# Stabilizer_Piezo_Driver.net
KiCad netlist of a schematic drawn in Altium Designer
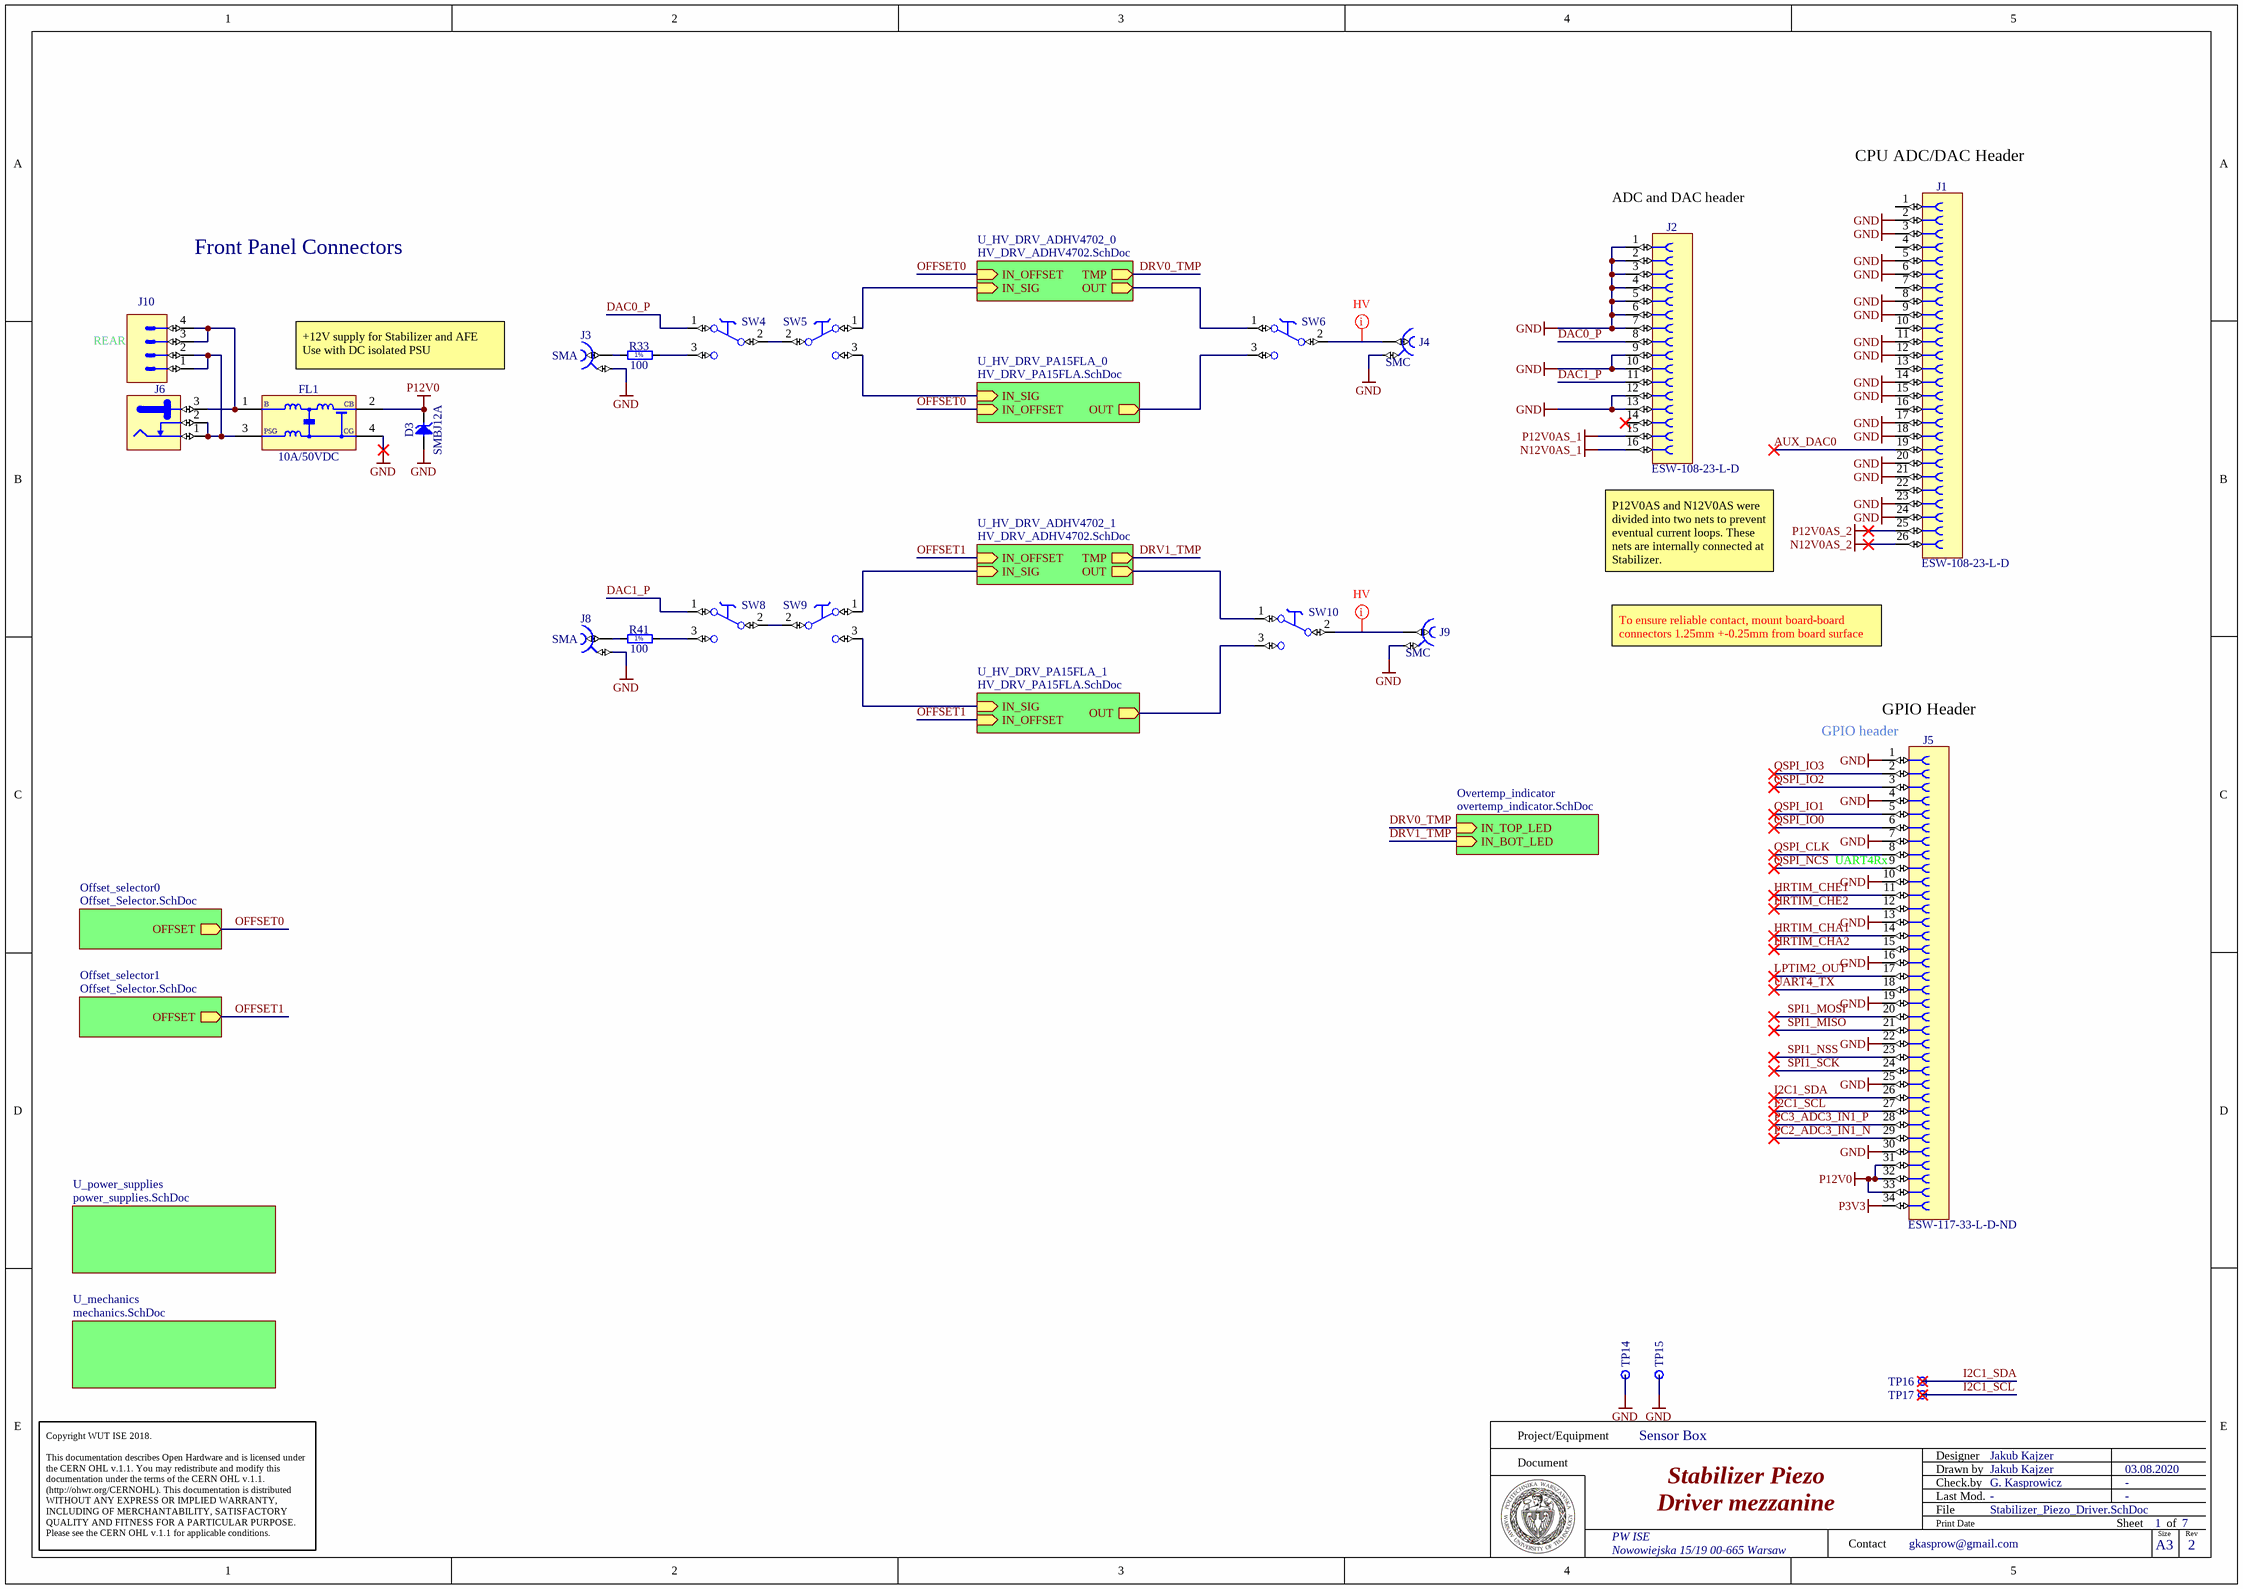
[diagram p0: Stabilizer_Piezo_Driver.SchDoc]

(export (version "E")
  (design (tool "Eeschema 10.0.6"))
  (components
    (comp (ref "D3")
      (value "SMBJ12A")
      (footprint "DIOM5336X265N")
      (description "Zener Diode")
      (fields
        (field (name "VOLTAGE") "12V")
        (field (name "POWER") "600W")
        (field (name "AUTHOR") "CERN DEM JLC")
      )
      (libsource (lib "ICs And Semiconductors") (part "Diode Zener"))
    )
    (comp (ref "FL1")
      (value "10A/50VDC")
      (footprint "FIL_MURATA_BNX02")
      (description "Block Type EMIFIL (LC Combined)")
      (fields
        (field (name "PART NUMBER") "FIL_MURATA_BNX022-01L")
        (field (name "MANUFACTURER") "MURATA")
        (field (name "AUTHOR") "CERN DEM JLC")
      )
      (libsource (lib "Inductors & Transformers") (part "FIL_MURATA_BNX02"))
    )
    (comp (ref "J1")
      (value "ESW-108-23-L-D")
      (footprint "connectors:ESW-113-23-L-D")
      (description "Connector Elevated Socket 26 POS 2.54mm, 13.59mm height")
      (fields
        (field (name "MANUFACTURER") "Samtec")
        (field (name "MANUFACTURER PART NUMBER") "ESW-108-23-L-D")
      )
      (libsource (lib "connectors") (part "ESW-113-23-L-D"))
    )
    (comp (ref "J2")
      (value "ESW-108-23-L-D")
      (footprint "connectors:ESW-108-23-L-D")
      (description "Connector Elevated Socket 16 POS 2.54mm, 13.59mm height")
      (fields
        (field (name "MANUFACTURER") "Samtec")
        (field (name "MANUFACTURER PART NUMBER") "ESW-108-23-L-D")
      )
      (libsource (lib "connectors") (part "ESW-108-23-L-D"))
    )
    (comp (ref "J3")
      (value "SMA")
      (footprint "RF249BT0050GHDW")
      (description "50 Ohm Through Hole SMA Right Angle PCB Jack")
      (fields
        (field (name "PART NUMBER") "AdamTech_RF249BT0050GHDW")
        (field (name "MANUFACTURER") "AdamTech")
        (field (name "AUTHOR") "GK")
      )
      (libsource (lib "LIBRARY_SCH") (part "CON_SMA_RF249BT0050GHDW"))
    )
    (comp (ref "J4")
      (value "SMC")
      (footprint "JOHNSON_131-6701-341")
      (fields
        (field (name "PART NUMBER") "JOHNSON_131-6701-341")
        (field (name "MANUFACTURER") "JOHNSON")
        (field (name "MANUFACTURER PART NUMBER") "131-6701-341")
        (field (name "AUTHOR") "CERN DEM JLC")
      )
      (libsource (lib "Connectors") (part "Coax_1Female_1Shield"))
    )
    (comp (ref "J5")
      (value "ESW-108-23-L-D")
      (footprint "connectors:ESW-117-23-L-D")
      (description "Connector Elevated Socket 34 POS 2.54mm, 13.59mm height")
      (fields
        (field (name "MANUFACTURER") "Samtec")
        (field (name "MANUFACTURER PART NUMBER") "ESW-117-33-L-D-ND")
      )
      (libsource (lib "connectors") (part "ESW-117-23-L-D"))
    )
    (comp (ref "J6")
      (value "Jack")
      (footprint "Library-connectors:SWITCHCRAFT_L712RA")
      (description "24V /3. 5A, 2.1mm Diameter Pin, SMD DC Power Supply Connector With  Break Contact")
      (fields
        (field (name "PART NUMBER") "SWITCHCRAFT_L712RA")
        (field (name "MANUFACTURER") "SWITCHCRAFT")
        (field (name "AUTHOR") "GK")
      )
      (libsource (lib "LIBRARY_SCH") (part "CON_DC_5A_THT_RA"))
    )
    (comp (ref "J8")
      (value "SMA")
      (footprint "RF249BT0050GHDW")
      (description "50 Ohm Through Hole SMA Right Angle PCB Jack")
      (fields
        (field (name "PART NUMBER") "AdamTech_RF249BT0050GHDW")
        (field (name "MANUFACTURER") "AdamTech")
        (field (name "AUTHOR") "GK")
      )
      (libsource (lib "LIBRARY_SCH") (part "CON_SMA_RF249BT0050GHDW"))
    )
    (comp (ref "J9")
      (value "SMC")
      (footprint "JOHNSON_131-6701-341")
      (fields
        (field (name "PART NUMBER") "JOHNSON_131-6701-341")
        (field (name "MANUFACTURER") "JOHNSON")
        (field (name "MANUFACTURER PART NUMBER") "131-6701-341")
        (field (name "AUTHOR") "CERN DEM JLC")
      )
      (libsource (lib "Connectors") (part "Coax_1Female_1Shield"))
    )
    (comp (ref "J10")
      (value "Mini-Fit Jr.™")
      (footprint "MOLEX_39-30-0040")
      (description "Connector 4 Male")
      (fields
        (field (name "PART NUMBER") "MOLEX_39-30-0040")
        (field (name "MANUFACTURER") "MOLEX")
        (field (name "AUTHOR") "CERN DEM JLC")
      )
      (libsource (lib "Connectors") (part "Connector 4 Male"))
    )
    (comp (ref "R33")
      (value "100")
      (footprint "RESC1005X40N")
      (description "Resistor - 1%")
      (fields
        (field (name "PART NUMBER") "R0402_100R_1%_0.0625W_100PPM")
        (field (name "POWER") "0.0625W")
        (field (name "AUTHOR") "CERN DEM JLC")
      )
      (libsource (lib "Resistors") (part "Resistor - 1%"))
    )
    (comp (ref "R41")
      (value "100")
      (footprint "RESC1005X40N")
      (description "Resistor - 1%")
      (fields
        (field (name "PART NUMBER") "R0402_100R_1%_0.0625W_100PPM")
        (field (name "POWER") "0.0625W")
        (field (name "AUTHOR") "CERN DEM JLC")
      )
      (libsource (lib "Resistors") (part "Resistor - 1%"))
    )
    (comp (ref "SW4")
      (value "Switch")
      (footprint "SW_C&K_1101M2S3CQE2")
      (description "SPDT Switch")
      (fields
        (field (name "PART NUMBER") "SW_C&K_1101M2S3CQE2")
        (field (name "MANUFACTURER") "C&K")
        (field (name "AUTHOR") "CERN DEM BC")
      )
      (libsource (lib "Eletro-mechanical") (part "SW SPDT 1NC-2C-3NO"))
    )
    (comp (ref "SW5")
      (value "Switch")
      (footprint "SW_C&K_1101M2S3CQE2")
      (description "SPDT Switch")
      (fields
        (field (name "PART NUMBER") "SW_C&K_1101M2S3CQE2")
        (field (name "MANUFACTURER") "C&K")
        (field (name "AUTHOR") "CERN DEM BC")
      )
      (libsource (lib "Eletro-mechanical") (part "SW SPDT 1NC-2C-3NO"))
    )
    (comp (ref "SW6")
      (value "Switch")
      (footprint "SW_C&K_1101M2S3CQE2")
      (description "SPDT Switch")
      (fields
        (field (name "PART NUMBER") "SW_C&K_1101M2S3CQE2")
        (field (name "MANUFACTURER") "C&K")
        (field (name "AUTHOR") "CERN DEM BC")
      )
      (libsource (lib "Eletro-mechanical") (part "SW SPDT 1NC-2C-3NO"))
    )
    (comp (ref "SW8")
      (value "Switch")
      (footprint "SW_C&K_1101M2S3CQE2")
      (description "SPDT Switch")
      (fields
        (field (name "PART NUMBER") "SW_C&K_1101M2S3CQE2")
        (field (name "MANUFACTURER") "C&K")
        (field (name "AUTHOR") "CERN DEM BC")
      )
      (libsource (lib "Eletro-mechanical") (part "SW SPDT 1NC-2C-3NO"))
    )
    (comp (ref "SW9")
      (value "Switch")
      (footprint "SW_C&K_1101M2S3CQE2")
      (description "SPDT Switch")
      (fields
        (field (name "PART NUMBER") "SW_C&K_1101M2S3CQE2")
        (field (name "MANUFACTURER") "C&K")
        (field (name "AUTHOR") "CERN DEM BC")
      )
      (libsource (lib "Eletro-mechanical") (part "SW SPDT 1NC-2C-3NO"))
    )
    (comp (ref "SW10")
      (value "Switch")
      (footprint "SW_C&K_1101M2S3CQE2")
      (description "SPDT Switch")
      (fields
        (field (name "PART NUMBER") "SW_C&K_1101M2S3CQE2")
        (field (name "MANUFACTURER") "C&K")
        (field (name "AUTHOR") "CERN DEM BC")
      )
      (libsource (lib "Eletro-mechanical") (part "SW SPDT 1NC-2C-3NO"))
    )
    (comp (ref "TP14")
      (value "Test Point")
      (footprint "TPS127")
      (fields (field (name "PART NUMBER") "SMD_PAD_1.27X1.27MM") (field (name "AUTHOR") "CERN DEM JLC"))
      (libsource (lib "Eletro-mechanical") (part "Test Point"))
    )
    (comp (ref "TP15")
      (value "Test Point")
      (footprint "TPS127")
      (fields (field (name "PART NUMBER") "SMD_PAD_1.27X1.27MM") (field (name "AUTHOR") "CERN DEM JLC"))
      (libsource (lib "Eletro-mechanical") (part "Test Point"))
    )
    (comp (ref "TP16")
      (value "Test Point")
      (footprint "TPS127")
      (fields (field (name "PART NUMBER") "SMD_PAD_1.27X1.27MM") (field (name "AUTHOR") "CERN DEM JLC"))
      (libsource (lib "Eletro-mechanical") (part "Test Point"))
    )
    (comp (ref "TP17")
      (value "Test Point")
      (footprint "TPS127")
      (fields (field (name "PART NUMBER") "SMD_PAD_1.27X1.27MM") (field (name "AUTHOR") "CERN DEM JLC"))
      (libsource (lib "Eletro-mechanical") (part "Test Point"))
    )
  )
  (nets
    (net (code "1") (name "/AUX_DAC0") (class "Default")
      (node (ref "J1") (pin "19") (pinfunction "19_19") (pintype "bidirectional+no_connect"))
    )
    (net (code "2") (name "/DAC0_P") (class "Default")
      (node (ref "J2") (pin "8") (pinfunction "8_8") (pintype "bidirectional"))
      (node (ref "SW4") (pin "1") (pinfunction "NC_1") (pintype "bidirectional"))
    )
    (net (code "3") (name "/DAC1_P") (class "Default")
      (node (ref "J2") (pin "11") (pinfunction "11_11") (pintype "bidirectional"))
      (node (ref "SW8") (pin "1") (pinfunction "NC_1") (pintype "bidirectional"))
    )
    (net (code "6") (name "/HRTIM_CHA1") (class "Default")
      (node (ref "J5") (pin "14") (pinfunction "14_14") (pintype "bidirectional+no_connect"))
    )
    (net (code "7") (name "/HRTIM_CHA2") (class "Default")
      (node (ref "J5") (pin "15") (pinfunction "15_15") (pintype "bidirectional+no_connect"))
    )
    (net (code "8") (name "/HRTIM_CHE1") (class "Default")
      (node (ref "J5") (pin "11") (pinfunction "11_11") (pintype "bidirectional+no_connect"))
    )
    (net (code "9") (name "/HRTIM_CHE2") (class "Default")
      (node (ref "J5") (pin "12") (pinfunction "12_12") (pintype "bidirectional+no_connect"))
    )
    (net (code "10") (name "/I2C1_SCL") (class "Default")
      (node (ref "J5") (pin "27") (pinfunction "27_27") (pintype "bidirectional"))
      (node (ref "TP17") (pin "1") (pinfunction "1_1") (pintype "bidirectional"))
    )
    (net (code "11") (name "/I2C1_SDA") (class "Default")
      (node (ref "J5") (pin "26") (pinfunction "26_26") (pintype "bidirectional"))
      (node (ref "TP16") (pin "1") (pinfunction "1_1") (pintype "bidirectional"))
    )
    (net (code "12") (name "/IN_SIG") (class "Default")
      (node (ref "SW5") (pin "3") (pinfunction "NO_3") (pintype "bidirectional"))
    )
    (net (code "13") (name "/IN_SIG_1") (class "Default")
      (node (ref "SW9") (pin "1") (pinfunction "NC_1") (pintype "bidirectional"))
    )
    (net (code "14") (name "/IN_SIG_2") (class "Default")
      (node (ref "SW9") (pin "3") (pinfunction "NO_3") (pintype "bidirectional"))
    )
    (net (code "15") (name "/IN_SIG_3") (class "Default")
      (node (ref "SW5") (pin "1") (pinfunction "NC_1") (pintype "bidirectional"))
    )
    (net (code "16") (name "/LPTIM2_OUT") (class "Default")
      (node (ref "J5") (pin "17") (pinfunction "17_17") (pintype "bidirectional+no_connect"))
    )
    (net (code "19") (name "/OUT") (class "Default")
      (node (ref "SW10") (pin "1") (pinfunction "NC_1") (pintype "bidirectional"))
    )
    (net (code "20") (name "/OUT_1") (class "Default")
      (node (ref "SW10") (pin "3") (pinfunction "NO_3") (pintype "bidirectional"))
    )
    (net (code "21") (name "/OUT_2") (class "Default")
      (node (ref "SW6") (pin "1") (pinfunction "NC_1") (pintype "bidirectional"))
    )
    (net (code "22") (name "/OUT_3") (class "Default")
      (node (ref "SW6") (pin "3") (pinfunction "NO_3") (pintype "bidirectional"))
    )
    (net (code "23") (name "/PC2_ADC3_IN1_N") (class "Default")
      (node (ref "J5") (pin "29") (pinfunction "29_29") (pintype "bidirectional+no_connect"))
    )
    (net (code "24") (name "/PC3_ADC3_IN1_P") (class "Default")
      (node (ref "J5") (pin "28") (pinfunction "28_28") (pintype "bidirectional+no_connect"))
    )
    (net (code "25") (name "/QSPI_CLK") (class "Default")
      (node (ref "J5") (pin "8") (pinfunction "8_8") (pintype "bidirectional+no_connect"))
    )
    (net (code "26") (name "/QSPI_IO0") (class "Default")
      (node (ref "J5") (pin "6") (pinfunction "6_6") (pintype "bidirectional+no_connect"))
    )
    (net (code "27") (name "/QSPI_IO1") (class "Default")
      (node (ref "J5") (pin "5") (pinfunction "5_5") (pintype "bidirectional+no_connect"))
    )
    (net (code "28") (name "/QSPI_IO2") (class "Default")
      (node (ref "J5") (pin "3") (pinfunction "3_3") (pintype "bidirectional+no_connect"))
    )
    (net (code "29") (name "/QSPI_IO3") (class "Default")
      (node (ref "J5") (pin "2") (pinfunction "2_2") (pintype "bidirectional+no_connect"))
    )
    (net (code "30") (name "/QSPI_NCS") (class "Default")
      (node (ref "J5") (pin "9") (pinfunction "9_9") (pintype "bidirectional+no_connect"))
    )
    (net (code "31") (name "/SPI1_MISO") (class "Default")
      (node (ref "J5") (pin "21") (pinfunction "21_21") (pintype "bidirectional+no_connect"))
    )
    (net (code "32") (name "/SPI1_MOSI") (class "Default")
      (node (ref "J5") (pin "20") (pinfunction "20_20") (pintype "bidirectional+no_connect"))
    )
    (net (code "33") (name "/SPI1_NSS") (class "Default")
      (node (ref "J5") (pin "23") (pinfunction "23_23") (pintype "bidirectional+no_connect"))
    )
    (net (code "34") (name "/SPI1_SCK") (class "Default")
      (node (ref "J5") (pin "24") (pinfunction "24_24") (pintype "bidirectional+no_connect"))
    )
    (net (code "35") (name "/UART4_TX") (class "Default")
      (node (ref "J5") (pin "18") (pinfunction "18_18") (pintype "bidirectional+no_connect"))
    )
    (net (code "36") (name "GND") (class "Default")
      (node (ref "D3") (pin "2") (pinfunction "A_2") (pintype "passive"))
      (node (ref "FL1") (pin "4") (pinfunction "CG_4") (pintype "passive"))
      (node (ref "J1") (pin "11") (pinfunction "11_11") (pintype "bidirectional"))
      (node (ref "J1") (pin "12") (pinfunction "12_12") (pintype "bidirectional"))
      (node (ref "J1") (pin "14") (pinfunction "14_14") (pintype "bidirectional"))
      (node (ref "J1") (pin "15") (pinfunction "15_15") (pintype "bidirectional"))
      (node (ref "J1") (pin "17") (pinfunction "17_17") (pintype "bidirectional"))
      (node (ref "J1") (pin "18") (pinfunction "18_18") (pintype "bidirectional"))
      (node (ref "J1") (pin "2") (pinfunction "2_2") (pintype "bidirectional"))
      (node (ref "J1") (pin "20") (pinfunction "20_20") (pintype "bidirectional"))
      (node (ref "J1") (pin "21") (pinfunction "21_21") (pintype "bidirectional"))
      (node (ref "J1") (pin "23") (pinfunction "23_23") (pintype "bidirectional"))
      (node (ref "J1") (pin "24") (pinfunction "24_24") (pintype "bidirectional"))
      (node (ref "J1") (pin "3") (pinfunction "3_3") (pintype "bidirectional"))
      (node (ref "J1") (pin "5") (pinfunction "5_5") (pintype "bidirectional"))
      (node (ref "J1") (pin "6") (pinfunction "6_6") (pintype "bidirectional"))
      (node (ref "J1") (pin "8") (pinfunction "8_8") (pintype "bidirectional"))
      (node (ref "J1") (pin "9") (pinfunction "9_9") (pintype "bidirectional"))
      (node (ref "J2") (pin "1") (pinfunction "1_1") (pintype "bidirectional"))
      (node (ref "J2") (pin "10") (pinfunction "10_10") (pintype "bidirectional"))
      (node (ref "J2") (pin "12") (pinfunction "12_12") (pintype "bidirectional"))
      (node (ref "J2") (pin "13") (pinfunction "13_13") (pintype "bidirectional"))
      (node (ref "J2") (pin "2") (pinfunction "2_2") (pintype "bidirectional"))
      (node (ref "J2") (pin "3") (pinfunction "3_3") (pintype "bidirectional"))
      (node (ref "J2") (pin "4") (pinfunction "4_4") (pintype "bidirectional"))
      (node (ref "J2") (pin "5") (pinfunction "5_5") (pintype "bidirectional"))
      (node (ref "J2") (pin "6") (pinfunction "6_6") (pintype "bidirectional"))
      (node (ref "J2") (pin "7") (pinfunction "7_7") (pintype "bidirectional"))
      (node (ref "J2") (pin "9") (pinfunction "9_9") (pintype "bidirectional"))
      (node (ref "J3") (pin "2") (pinfunction "2_2") (pintype "bidirectional"))
      (node (ref "J4") (pin "2") (pinfunction "2_2") (pintype "bidirectional"))
      (node (ref "J5") (pin "1") (pinfunction "1_1") (pintype "bidirectional"))
      (node (ref "J5") (pin "10") (pinfunction "10_10") (pintype "bidirectional"))
      (node (ref "J5") (pin "13") (pinfunction "13_13") (pintype "bidirectional"))
      (node (ref "J5") (pin "16") (pinfunction "16_16") (pintype "bidirectional"))
      (node (ref "J5") (pin "19") (pinfunction "19_19") (pintype "bidirectional"))
      (node (ref "J5") (pin "22") (pinfunction "22_22") (pintype "bidirectional"))
      (node (ref "J5") (pin "25") (pinfunction "25_25") (pintype "bidirectional"))
      (node (ref "J5") (pin "30") (pinfunction "30_30") (pintype "bidirectional"))
      (node (ref "J5") (pin "4") (pinfunction "4_4") (pintype "bidirectional"))
      (node (ref "J5") (pin "7") (pinfunction "7_7") (pintype "bidirectional"))
      (node (ref "J8") (pin "2") (pinfunction "2_2") (pintype "bidirectional"))
      (node (ref "J9") (pin "2") (pinfunction "2_2") (pintype "bidirectional"))
      (node (ref "TP14") (pin "1") (pinfunction "1_1") (pintype "bidirectional"))
      (node (ref "TP15") (pin "1") (pinfunction "1_1") (pintype "bidirectional"))
    )
    (net (code "37") (name "N12V0AS_1") (class "Default")
      (node (ref "J2") (pin "16") (pinfunction "16_16") (pintype "bidirectional"))
    )
    (net (code "38") (name "N12V0AS_2") (class "Default")
      (node (ref "J1") (pin "26") (pinfunction "26_26") (pintype "bidirectional"))
    )
    (net (code "39") (name "Net-(FL1-B)") (class "Default")
      (node (ref "FL1") (pin "1") (pinfunction "B_1") (pintype "passive"))
      (node (ref "J10") (pin "3") (pinfunction "3_3") (pintype "bidirectional"))
      (node (ref "J10") (pin "4") (pinfunction "4_4") (pintype "bidirectional"))
      (node (ref "J6") (pin "3") (pinfunction "3_3") (pintype "bidirectional"))
    )
    (net (code "40") (name "Net-(FL1-PSG)") (class "Default")
      (node (ref "FL1") (pin "3") (pinfunction "PSG_3") (pintype "passive"))
      (node (ref "J10") (pin "1") (pinfunction "1_1") (pintype "bidirectional"))
      (node (ref "J10") (pin "2") (pinfunction "2_2") (pintype "bidirectional"))
      (node (ref "J6") (pin "1") (pinfunction "1_1") (pintype "bidirectional"))
      (node (ref "J6") (pin "2") (pinfunction "2_2") (pintype "bidirectional"))
    )
    (net (code "41") (name "Net-(J3-Pad1)") (class "Default")
      (node (ref "J3") (pin "1") (pinfunction "1_1") (pintype "bidirectional"))
      (node (ref "R33") (pin "1") (pinfunction "1_1") (pintype "passive"))
    )
    (net (code "42") (name "Net-(J8-Pad1)") (class "Default")
      (node (ref "J8") (pin "1") (pinfunction "1_1") (pintype "bidirectional"))
      (node (ref "R41") (pin "1") (pinfunction "1_1") (pintype "passive"))
    )
    (net (code "43") (name "Net-(SW4-C)") (class "Default")
      (node (ref "SW4") (pin "2") (pinfunction "C_2") (pintype "bidirectional"))
      (node (ref "SW5") (pin "2") (pinfunction "C_2") (pintype "bidirectional"))
    )
    (net (code "44") (name "Net-(SW4-NO)") (class "Default")
      (node (ref "R33") (pin "2") (pinfunction "2_2") (pintype "passive"))
      (node (ref "SW4") (pin "3") (pinfunction "NO_3") (pintype "bidirectional"))
    )
    (net (code "45") (name "Net-(SW6-C)") (class "Default")
      (node (ref "J4") (pin "1") (pinfunction "1_1") (pintype "bidirectional"))
      (node (ref "SW6") (pin "2") (pinfunction "C_2") (pintype "bidirectional"))
    )
    (net (code "46") (name "Net-(SW8-C)") (class "Default")
      (node (ref "SW8") (pin "2") (pinfunction "C_2") (pintype "bidirectional"))
      (node (ref "SW9") (pin "2") (pinfunction "C_2") (pintype "bidirectional"))
    )
    (net (code "47") (name "Net-(SW8-NO)") (class "Default")
      (node (ref "R41") (pin "2") (pinfunction "2_2") (pintype "passive"))
      (node (ref "SW8") (pin "3") (pinfunction "NO_3") (pintype "bidirectional"))
    )
    (net (code "48") (name "Net-(SW10-C)") (class "Default")
      (node (ref "J9") (pin "1") (pinfunction "1_1") (pintype "bidirectional"))
      (node (ref "SW10") (pin "2") (pinfunction "C_2") (pintype "bidirectional"))
    )
    (net (code "49") (name "P3V3") (class "Default")
      (node (ref "J5") (pin "34") (pinfunction "34_34") (pintype "bidirectional"))
    )
    (net (code "50") (name "P12V0") (class "Default")
      (node (ref "D3") (pin "1") (pinfunction "C_1") (pintype "passive"))
      (node (ref "FL1") (pin "2") (pinfunction "CB_2") (pintype "passive"))
      (node (ref "J5") (pin "31") (pinfunction "31_31") (pintype "bidirectional"))
      (node (ref "J5") (pin "32") (pinfunction "32_32") (pintype "bidirectional"))
      (node (ref "J5") (pin "33") (pinfunction "33_33") (pintype "bidirectional"))
    )
    (net (code "51") (name "P12V0AS_1") (class "Default")
      (node (ref "J2") (pin "15") (pinfunction "15_15") (pintype "bidirectional"))
    )
    (net (code "52") (name "P12V0AS_2") (class "Default")
      (node (ref "J1") (pin "25") (pinfunction "25_25") (pintype "bidirectional"))
    )
    (net (code "53") (name "unconnected-(J1-Pad1)") (class "Default")
      (node (ref "J1") (pin "1") (pinfunction "1_1") (pintype "bidirectional"))
    )
    (net (code "54") (name "unconnected-(J1-Pad4)") (class "Default")
      (node (ref "J1") (pin "4") (pinfunction "4_4") (pintype "bidirectional"))
    )
    (net (code "55") (name "unconnected-(J1-Pad7)") (class "Default")
      (node (ref "J1") (pin "7") (pinfunction "7_7") (pintype "bidirectional"))
    )
    (net (code "56") (name "unconnected-(J1-Pad10)") (class "Default")
      (node (ref "J1") (pin "10") (pinfunction "10_10") (pintype "bidirectional"))
    )
    (net (code "57") (name "unconnected-(J1-Pad13)") (class "Default")
      (node (ref "J1") (pin "13") (pinfunction "13_13") (pintype "bidirectional"))
    )
    (net (code "58") (name "unconnected-(J1-Pad16)") (class "Default")
      (node (ref "J1") (pin "16") (pinfunction "16_16") (pintype "bidirectional"))
    )
    (net (code "59") (name "unconnected-(J1-Pad22)") (class "Default")
      (node (ref "J1") (pin "22") (pinfunction "22_22") (pintype "bidirectional"))
    )
    (net (code "60") (name "unconnected-(J2-Pad14)") (class "Default")
      (node (ref "J2") (pin "14") (pinfunction "14_14") (pintype "bidirectional+no_connect"))
    )
  )
)
